# pcb_univ_3-6-0-x-rev5.net
KiCad netlist of a schematic drawn in EAGLE
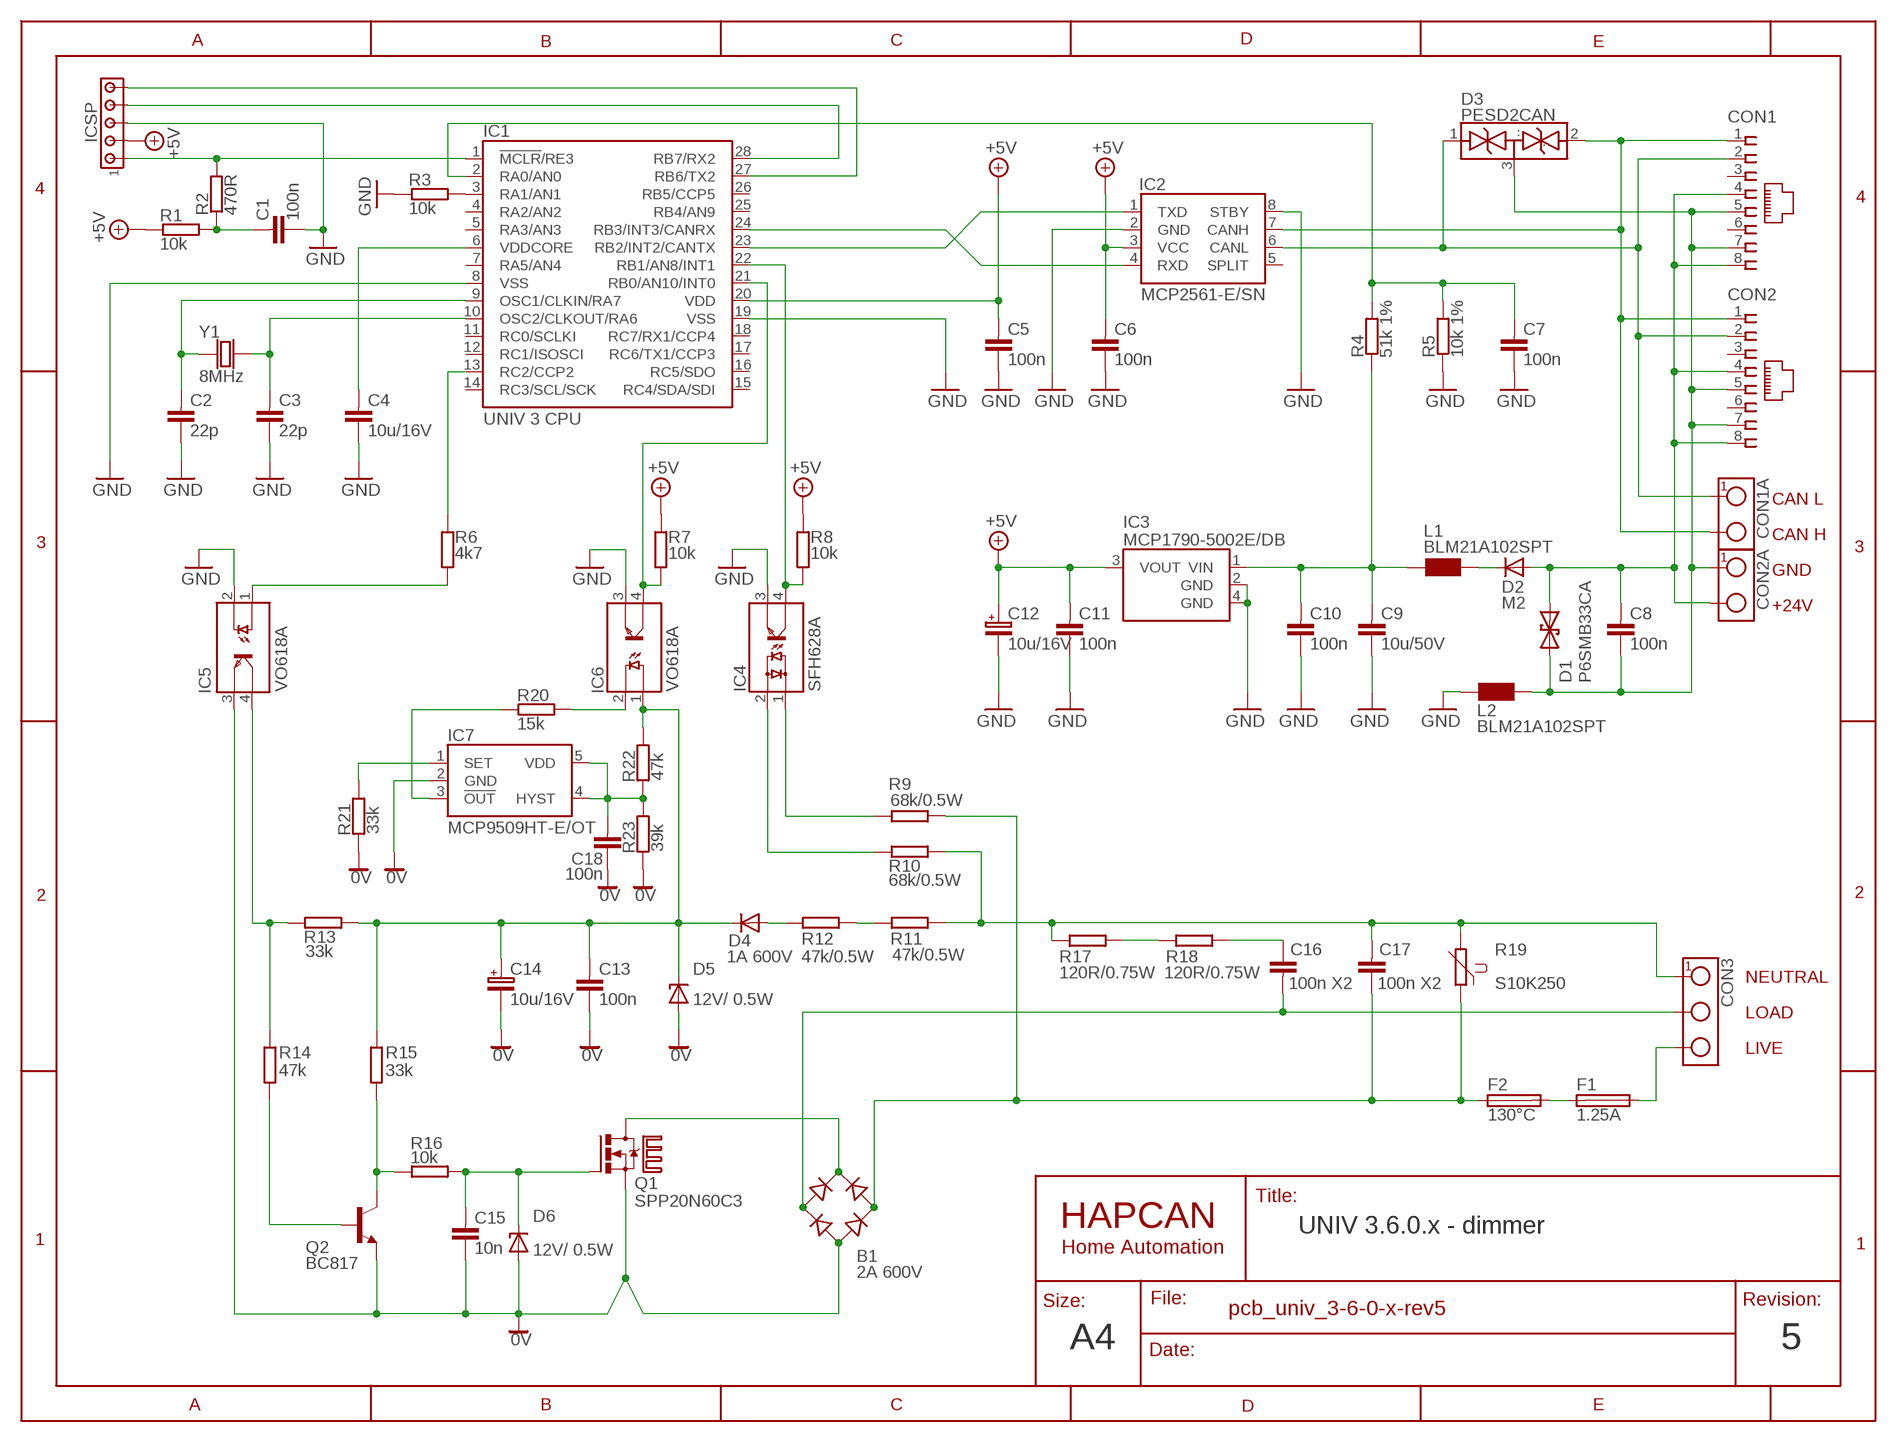
[diagram p0: schematic, sheet 1]

(export (version "E")
  (design (tool "Eeschema 10.0.6"))
  (components
    (comp (ref "B1")
      (value "2A 600V")
      (footprint "eagle-import:RECTIFIER_KBP")
      (libsource (lib "eagle-import") (part "DIODE_BRIDGE-5.0"))
    )
    (comp (ref "C1")
      (value "100n")
      (footprint "eagle-import:0805")
      (libsource (lib "eagle-import") (part "CAPACITOR0805"))
    )
    (comp (ref "C2")
      (value "22p")
      (footprint "eagle-import:0805")
      (libsource (lib "eagle-import") (part "CAPACITOR0805"))
    )
    (comp (ref "C3")
      (value "22p")
      (footprint "eagle-import:0805")
      (libsource (lib "eagle-import") (part "CAPACITOR0805"))
    )
    (comp (ref "C4")
      (value "10u/16V")
      (footprint "eagle-import:0805")
      (libsource (lib "eagle-import") (part "CAPACITOR0805"))
    )
    (comp (ref "C5")
      (value "100n")
      (footprint "eagle-import:0805")
      (libsource (lib "eagle-import") (part "CAPACITOR0805"))
    )
    (comp (ref "C6")
      (value "100n")
      (footprint "eagle-import:0805")
      (libsource (lib "eagle-import") (part "CAPACITOR0805"))
    )
    (comp (ref "C7")
      (value "100n")
      (footprint "eagle-import:0805")
      (libsource (lib "eagle-import") (part "CAPACITOR0805"))
    )
    (comp (ref "C8")
      (value "100n")
      (footprint "eagle-import:0805")
      (libsource (lib "eagle-import") (part "CAPACITOR0805"))
    )
    (comp (ref "C9")
      (value "10u/50V")
      (footprint "eagle-import:1210")
      (libsource (lib "eagle-import") (part "CAPACITOR1210"))
    )
    (comp (ref "C10")
      (value "100n")
      (footprint "eagle-import:0805")
      (libsource (lib "eagle-import") (part "CAPACITOR0805"))
    )
    (comp (ref "C11")
      (value "100n")
      (footprint "eagle-import:0805")
      (libsource (lib "eagle-import") (part "CAPACITOR0805"))
    )
    (comp (ref "C12")
      (value "10u/16V")
      (footprint "eagle-import:SMC_B")
      (libsource (lib "eagle-import") (part "CAPACITOR-POLARIZED-SMC_B"))
    )
    (comp (ref "C13")
      (value "100n")
      (footprint "eagle-import:0805")
      (libsource (lib "eagle-import") (part "CAPACITOR0805"))
    )
    (comp (ref "C14")
      (value "10u/16V")
      (footprint "eagle-import:SMC_B")
      (libsource (lib "eagle-import") (part "CAPACITOR-POLARIZED-SMC_B"))
    )
    (comp (ref "C15")
      (value "10n")
      (footprint "eagle-import:0805")
      (libsource (lib "eagle-import") (part "CAPACITOR0805"))
    )
    (comp (ref "C16")
      (value "100n X2")
      (footprint "eagle-import:CAP-15X5")
      (libsource (lib "eagle-import") (part "CAPACITOR15X5"))
    )
    (comp (ref "C17")
      (value "100n X2")
      (footprint "eagle-import:CAP-15X5")
      (libsource (lib "eagle-import") (part "CAPACITOR15X5"))
    )
    (comp (ref "C18")
      (value "100n")
      (footprint "eagle-import:0805")
      (libsource (lib "eagle-import") (part "CAPACITOR0805"))
    )
    (comp (ref "CON1")
      (value "RJ45-SOCKET")
      (footprint "eagle-import:RJ45-PCB-SOCKET")
      (libsource (lib "eagle-import") (part "RJ45-SOCKET"))
    )
    (comp (ref "CON1A")
      (value "TERMINAL-2")
      (footprint "eagle-import:ARK2-5X10,5MM")
      (libsource (lib "eagle-import") (part "TERMINAL-2-5X10,5MM"))
    )
    (comp (ref "CON2")
      (value "RJ45-SOCKET")
      (footprint "eagle-import:RJ45-PCB-SOCKET")
      (libsource (lib "eagle-import") (part "RJ45-SOCKET"))
    )
    (comp (ref "CON2A")
      (value "TERMINAL-2")
      (footprint "eagle-import:ARK2-5X10,5MM")
      (libsource (lib "eagle-import") (part "TERMINAL-2-5X10,5MM"))
    )
    (comp (ref "CON3")
      (value "TERMINAL-3")
      (footprint "eagle-import:ARK3-5X10.5MM")
      (libsource (lib "eagle-import") (part "TERMINAL-3-5X10.5MM"))
    )
    (comp (ref "D1")
      (value "P6SMB33CA")
      (footprint "eagle-import:DO-214_TRANSIL2")
      (libsource (lib "eagle-import") (part "DIODE_TRANSIL2"))
    )
    (comp (ref "D2")
      (value "M2")
      (footprint "eagle-import:DO-214")
      (libsource (lib "eagle-import") (part "DIODE_DO-214"))
    )
    (comp (ref "D3")
      (value "PESD2CAN")
      (footprint "eagle-import:SOT-23")
      (libsource (lib "eagle-import") (part "PESD2CANSOT-23"))
    )
    (comp (ref "D4")
      (value "1A 600V")
      (footprint "eagle-import:DO-213")
      (libsource (lib "eagle-import") (part "DIODE_MELF"))
    )
    (comp (ref "D5")
      (value "12V/ 0.5W")
      (footprint "eagle-import:SOD-80")
      (libsource (lib "eagle-import") (part "DIODE_ZENER_SOD-80"))
    )
    (comp (ref "D6")
      (value "12V/ 0.5W")
      (footprint "eagle-import:SOD-80")
      (libsource (lib "eagle-import") (part "DIODE_ZENER_SOD-80"))
    )
    (comp (ref "F1")
      (value "1.25A")
      (footprint "eagle-import:FUSE-HOLDER-V")
      (libsource (lib "eagle-import") (part "FUSE_V"))
    )
    (comp (ref "F2")
      (value "130°C")
      (footprint "eagle-import:FUSE-7.5")
      (libsource (lib "eagle-import") (part "FUSE"))
    )
    (comp (ref "IC1")
      (value "UNIV 3 CPU")
      (footprint "eagle-import:UNIV3CPU")
      (libsource (lib "eagle-import") (part "UNIV3CPU-I/SO"))
    )
    (comp (ref "IC2")
      (value "MCP2561-E/SN")
      (footprint "eagle-import:SO-08")
      (libsource (lib "eagle-import") (part "MCP2561-E/SN"))
    )
    (comp (ref "IC3")
      (value "MCP1790-5002E/DB")
      (footprint "eagle-import:SOT-223")
      (libsource (lib "eagle-import") (part "MCP1790"))
    )
    (comp (ref "IC4")
      (value "SFH628A")
      (footprint "eagle-import:DIL-04W")
      (libsource (lib "eagle-import") (part "COUPLER-1CH-AC_WIDE"))
    )
    (comp (ref "IC5")
      (value "VO618A")
      (footprint "eagle-import:DIL-04W")
      (libsource (lib "eagle-import") (part "COUPLER-1CH_04W"))
    )
    (comp (ref "IC6")
      (value "VO618A")
      (footprint "eagle-import:DIL-04W")
      (libsource (lib "eagle-import") (part "COUPLER-1CH_04W"))
    )
    (comp (ref "IC7")
      (value "MCP9509HT-E/OT")
      (footprint "eagle-import:SOT-23-5")
      (libsource (lib "eagle-import") (part "MCP9509"))
    )
    (comp (ref "ICSP")
      (value "HEADER5")
      (footprint "eagle-import:SIP-5")
      (libsource (lib "eagle-import") (part "HEADER5"))
    )
    (comp (ref "L1")
      (value "BLM21A102SPT")
      (footprint "eagle-import:0805")
      (libsource (lib "eagle-import") (part "CHOKE0805"))
    )
    (comp (ref "L2")
      (value "BLM21A102SPT")
      (footprint "eagle-import:0805")
      (libsource (lib "eagle-import") (part "CHOKE0805"))
    )
    (comp (ref "Q1")
      (value "SPP20N60C3")
      (footprint "eagle-import:TO220V-3")
      (libsource (lib "eagle-import") (part "TRANSISTOR_MOSFET_N_TO220V-3"))
    )
    (comp (ref "Q2")
      (value "BC817")
      (footprint "eagle-import:SOT-23")
      (libsource (lib "eagle-import") (part "TRANSISTOR_NPN"))
    )
    (comp (ref "R1")
      (value "10k")
      (footprint "eagle-import:0805")
      (libsource (lib "eagle-import") (part "RESISTOR0805"))
    )
    (comp (ref "R2")
      (value "470R")
      (footprint "eagle-import:0805")
      (libsource (lib "eagle-import") (part "RESISTOR0805"))
    )
    (comp (ref "R3")
      (value "10k")
      (footprint "eagle-import:0805")
      (libsource (lib "eagle-import") (part "RESISTOR0805"))
    )
    (comp (ref "R4")
      (value "51k 1%")
      (footprint "eagle-import:0805")
      (libsource (lib "eagle-import") (part "RESISTOR0805"))
    )
    (comp (ref "R5")
      (value "10k 1%")
      (footprint "eagle-import:0805")
      (libsource (lib "eagle-import") (part "RESISTOR0805"))
    )
    (comp (ref "R6")
      (value "4k7")
      (footprint "eagle-import:0805")
      (libsource (lib "eagle-import") (part "RESISTOR0805"))
    )
    (comp (ref "R7")
      (value "10k")
      (footprint "eagle-import:0805")
      (libsource (lib "eagle-import") (part "RESISTOR0805"))
    )
    (comp (ref "R8")
      (value "10k")
      (footprint "eagle-import:0805")
      (libsource (lib "eagle-import") (part "RESISTOR0805"))
    )
    (comp (ref "R9")
      (value "68k/0.5W")
      (footprint "eagle-import:2010")
      (libsource (lib "eagle-import") (part "RESISTOR2010"))
    )
    (comp (ref "R10")
      (value "68k/0.5W")
      (footprint "eagle-import:2010")
      (libsource (lib "eagle-import") (part "RESISTOR2010"))
    )
    (comp (ref "R11")
      (value "47k/0.5W")
      (footprint "eagle-import:2010")
      (libsource (lib "eagle-import") (part "RESISTOR2010"))
    )
    (comp (ref "R12")
      (value "47k/0.5W")
      (footprint "eagle-import:2010")
      (libsource (lib "eagle-import") (part "RESISTOR2010"))
    )
    (comp (ref "R13")
      (value "33k")
      (footprint "eagle-import:0805")
      (libsource (lib "eagle-import") (part "RESISTOR0805"))
    )
    (comp (ref "R14")
      (value "47k")
      (footprint "eagle-import:0805")
      (libsource (lib "eagle-import") (part "RESISTOR0805"))
    )
    (comp (ref "R15")
      (value "33k")
      (footprint "eagle-import:0805")
      (libsource (lib "eagle-import") (part "RESISTOR0805"))
    )
    (comp (ref "R16")
      (value "10k")
      (footprint "eagle-import:0805")
      (libsource (lib "eagle-import") (part "RESISTOR0805"))
    )
    (comp (ref "R17")
      (value "120R/0.75W")
      (footprint "eagle-import:2010")
      (libsource (lib "eagle-import") (part "RESISTOR2010"))
    )
    (comp (ref "R18")
      (value "120R/0.75W")
      (footprint "eagle-import:2010")
      (libsource (lib "eagle-import") (part "RESISTOR2010"))
    )
    (comp (ref "R19")
      (value "S10K250")
      (footprint "eagle-import:VARISTOR3")
      (libsource (lib "eagle-import") (part "VARISTOR7.5MM-2"))
    )
    (comp (ref "R20")
      (value "15k")
      (footprint "eagle-import:0805")
      (libsource (lib "eagle-import") (part "RESISTOR0805"))
    )
    (comp (ref "R21")
      (value "33k")
      (footprint "eagle-import:0805")
      (libsource (lib "eagle-import") (part "RESISTOR0805"))
    )
    (comp (ref "R22")
      (value "47k")
      (footprint "eagle-import:0805")
      (libsource (lib "eagle-import") (part "RESISTOR0805"))
    )
    (comp (ref "R23")
      (value "39k")
      (footprint "eagle-import:0805")
      (libsource (lib "eagle-import") (part "RESISTOR0805"))
    )
    (comp (ref "U$1")
      (value "HEATSINK_HS003")
      (footprint "eagle-import:HEATSINK_HS-003")
      (libsource (lib "eagle-import") (part "HEATSINK_HS003"))
    )
    (comp (ref "Y1")
      (value "8MHz")
      (footprint "eagle-import:CRYSTAL-HC49V")
      (libsource (lib "eagle-import") (part "CRYSTAL-HC49V"))
    )
  )
  (nets
    (net (code "1") (name "+5V") (class "Default")
      (node (ref "C11") (pin "1") (pinfunction "1_1") (pintype "passive"))
      (node (ref "C12") (pin "+") (pinfunction "1_+") (pintype "passive"))
      (node (ref "C5") (pin "1") (pinfunction "1_1") (pintype "passive"))
      (node (ref "C6") (pin "1") (pinfunction "1_1") (pintype "passive"))
      (node (ref "IC1") (pin "20") (pinfunction "VDD_20") (pintype "bidirectional"))
      (node (ref "IC2") (pin "3") (pinfunction "VCC_3") (pintype "bidirectional"))
      (node (ref "IC3") (pin "3") (pinfunction "VOUT_3") (pintype "bidirectional"))
      (node (ref "ICSP") (pin "2") (pinfunction "2_2") (pintype "passive"))
      (node (ref "R1") (pin "1") (pinfunction "1_1") (pintype "passive"))
      (node (ref "R7") (pin "2") (pinfunction "2_2") (pintype "passive"))
      (node (ref "R8") (pin "2") (pinfunction "2_2") (pintype "passive"))
    )
    (net (code "2") (name "0V") (class "Default")
      (node (ref "B1") (pin "-") (pinfunction "-_-") (pintype "passive"))
      (node (ref "C13") (pin "2") (pinfunction "2_2") (pintype "passive"))
      (node (ref "C14") (pin "-") (pinfunction "2_-") (pintype "passive"))
      (node (ref "C15") (pin "2") (pinfunction "2_2") (pintype "passive"))
      (node (ref "C18") (pin "2") (pinfunction "2_2") (pintype "passive"))
      (node (ref "D5") (pin "A") (pinfunction "A_A") (pintype "passive"))
      (node (ref "D6") (pin "A") (pinfunction "A_A") (pintype "passive"))
      (node (ref "IC5") (pin "3") (pinfunction "E_3") (pintype "bidirectional"))
      (node (ref "IC7") (pin "2") (pinfunction "GND_2") (pintype "bidirectional"))
      (node (ref "Q1") (pin "3") (pinfunction "S_3") (pintype "passive"))
      (node (ref "Q2") (pin "2") (pinfunction "E_2") (pintype "passive"))
      (node (ref "R21") (pin "2") (pinfunction "2_2") (pintype "passive"))
      (node (ref "R23") (pin "2") (pinfunction "2_2") (pintype "passive"))
    )
    (net (code "3") (name "GND") (class "Default")
      (node (ref "C1") (pin "2") (pinfunction "2_2") (pintype "passive"))
      (node (ref "C10") (pin "2") (pinfunction "2_2") (pintype "passive"))
      (node (ref "C11") (pin "2") (pinfunction "2_2") (pintype "passive"))
      (node (ref "C12") (pin "-") (pinfunction "2_-") (pintype "passive"))
      (node (ref "C2") (pin "2") (pinfunction "2_2") (pintype "passive"))
      (node (ref "C3") (pin "2") (pinfunction "2_2") (pintype "passive"))
      (node (ref "C4") (pin "2") (pinfunction "2_2") (pintype "passive"))
      (node (ref "C5") (pin "2") (pinfunction "2_2") (pintype "passive"))
      (node (ref "C6") (pin "2") (pinfunction "2_2") (pintype "passive"))
      (node (ref "C7") (pin "2") (pinfunction "2_2") (pintype "passive"))
      (node (ref "C9") (pin "2") (pinfunction "2_2") (pintype "passive"))
      (node (ref "IC1") (pin "19") (pinfunction "VSS_19") (pintype "bidirectional"))
      (node (ref "IC1") (pin "8") (pinfunction "VSS_8") (pintype "bidirectional"))
      (node (ref "IC2") (pin "2") (pinfunction "GND_2") (pintype "bidirectional"))
      (node (ref "IC2") (pin "8") (pinfunction "STBY_8") (pintype "bidirectional"))
      (node (ref "IC3") (pin "2") (pinfunction "GND_2") (pintype "bidirectional"))
      (node (ref "IC3") (pin "4") (pinfunction "GND_4") (pintype "bidirectional"))
      (node (ref "IC4") (pin "3") (pinfunction "E1_3") (pintype "bidirectional"))
      (node (ref "IC5") (pin "2") (pinfunction "K_2") (pintype "bidirectional"))
      (node (ref "IC6") (pin "3") (pinfunction "E_3") (pintype "bidirectional"))
      (node (ref "ICSP") (pin "3") (pinfunction "3_3") (pintype "passive"))
      (node (ref "L2") (pin "1") (pinfunction "1_1") (pintype "passive"))
      (node (ref "R3") (pin "1") (pinfunction "1_1") (pintype "passive"))
      (node (ref "R5") (pin "1") (pinfunction "1_1") (pintype "passive"))
    )
    (net (code "4") (name "Net-(B1-PadAC1)") (class "Default")
      (node (ref "B1") (pin "AC1") (pinfunction "AC1_AC1") (pintype "passive"))
      (node (ref "C16") (pin "1") (pinfunction "1_1") (pintype "passive"))
      (node (ref "CON3") (pin "2") (pinfunction "2_2") (pintype "passive"))
    )
    (net (code "5") (name "Net-(B1-PadAC2)") (class "Default")
      (node (ref "B1") (pin "AC2") (pinfunction "AC2_AC2") (pintype "passive"))
      (node (ref "C17") (pin "2") (pinfunction "2_2") (pintype "passive"))
      (node (ref "F2") (pin "1") (pinfunction "1_1") (pintype "passive"))
      (node (ref "R19") (pin "1") (pinfunction "1_1") (pintype "passive"))
      (node (ref "R9") (pin "2") (pinfunction "2_2") (pintype "passive"))
    )
    (net (code "6") (name "Net-(C1-Pad1)") (class "Default")
      (node (ref "C1") (pin "1") (pinfunction "1_1") (pintype "passive"))
      (node (ref "R1") (pin "2") (pinfunction "2_2") (pintype "passive"))
      (node (ref "R2") (pin "1") (pinfunction "1_1") (pintype "passive"))
    )
    (net (code "7") (name "Net-(C14-1)") (class "Default")
      (node (ref "C13") (pin "1") (pinfunction "1_1") (pintype "passive"))
      (node (ref "C14") (pin "+") (pinfunction "1_+") (pintype "passive"))
      (node (ref "D4") (pin "C") (pinfunction "C_C") (pintype "passive"))
      (node (ref "D5") (pin "C") (pinfunction "C_C") (pintype "passive"))
      (node (ref "IC6") (pin "1") (pinfunction "A_1") (pintype "bidirectional"))
      (node (ref "R13") (pin "2") (pinfunction "2_2") (pintype "passive"))
      (node (ref "R15") (pin "1") (pinfunction "1_1") (pintype "passive"))
      (node (ref "R22") (pin "2") (pinfunction "2_2") (pintype "passive"))
    )
    (net (code "8") (name "Net-(C16-Pad2)") (class "Default")
      (node (ref "C16") (pin "2") (pinfunction "2_2") (pintype "passive"))
      (node (ref "R18") (pin "1") (pinfunction "1_1") (pintype "passive"))
    )
    (net (code "9") (name "Net-(C17-Pad1)") (class "Default")
      (node (ref "C17") (pin "1") (pinfunction "1_1") (pintype "passive"))
      (node (ref "CON3") (pin "1") (pinfunction "1_1") (pintype "passive"))
      (node (ref "R10") (pin "2") (pinfunction "2_2") (pintype "passive"))
      (node (ref "R11") (pin "1") (pinfunction "1_1") (pintype "passive"))
      (node (ref "R17") (pin "2") (pinfunction "2_2") (pintype "passive"))
      (node (ref "R19") (pin "2") (pinfunction "2_2") (pintype "passive"))
    )
    (net (code "10") (name "Net-(CON3-Pad3)") (class "Default")
      (node (ref "CON3") (pin "3") (pinfunction "3_3") (pintype "passive"))
      (node (ref "F1") (pin "1") (pinfunction "1_1") (pintype "passive"))
    )
    (net (code "11") (name "Net-(D1-1)") (class "Default")
      (node (ref "C8") (pin "2") (pinfunction "2_2") (pintype "passive"))
      (node (ref "CON1") (pin "5") (pinfunction "5_5") (pintype "passive"))
      (node (ref "CON1") (pin "7") (pinfunction "7_7") (pintype "passive"))
      (node (ref "CON2") (pin "5") (pinfunction "5_5") (pintype "passive"))
      (node (ref "CON2") (pin "7") (pinfunction "7_7") (pintype "passive"))
      (node (ref "CON2A") (pin "1") (pinfunction "1_1") (pintype "passive"))
      (node (ref "D1") (pin "A") (pinfunction "1_A") (pintype "passive"))
      (node (ref "D3") (pin "3") (pinfunction "..._3") (pintype "bidirectional"))
      (node (ref "L2") (pin "2") (pinfunction "2_2") (pintype "passive"))
    )
    (net (code "12") (name "Net-(D1-2)") (class "Default")
      (node (ref "C8") (pin "1") (pinfunction "1_1") (pintype "passive"))
      (node (ref "CON1") (pin "4") (pinfunction "4_4") (pintype "passive"))
      (node (ref "CON1") (pin "8") (pinfunction "8_8") (pintype "passive"))
      (node (ref "CON2") (pin "4") (pinfunction "4_4") (pintype "passive"))
      (node (ref "CON2") (pin "8") (pinfunction "8_8") (pintype "passive"))
      (node (ref "CON2A") (pin "2") (pinfunction "2_2") (pintype "passive"))
      (node (ref "D1") (pin "C") (pinfunction "2_C") (pintype "passive"))
      (node (ref "D2") (pin "A") (pinfunction "A_A") (pintype "passive"))
    )
    (net (code "13") (name "Net-(D2-PadC)") (class "Default")
      (node (ref "D2") (pin "C") (pinfunction "C_C") (pintype "passive"))
      (node (ref "L1") (pin "2") (pinfunction "2_2") (pintype "passive"))
    )
    (net (code "14") (name "Net-(D3-.)") (class "Default")
      (node (ref "CON1") (pin "2") (pinfunction "2_2") (pintype "passive"))
      (node (ref "CON1A") (pin "1") (pinfunction "1_1") (pintype "passive"))
      (node (ref "CON2") (pin "2") (pinfunction "2_2") (pintype "passive"))
      (node (ref "D3") (pin "1") (pinfunction "._1") (pintype "bidirectional"))
      (node (ref "IC2") (pin "6") (pinfunction "CANL_6") (pintype "bidirectional"))
    )
    (net (code "15") (name "Net-(D3-..)") (class "Default")
      (node (ref "CON1") (pin "1") (pinfunction "1_1") (pintype "passive"))
      (node (ref "CON1A") (pin "2") (pinfunction "2_2") (pintype "passive"))
      (node (ref "CON2") (pin "1") (pinfunction "1_1") (pintype "passive"))
      (node (ref "D3") (pin "2") (pinfunction ".._2") (pintype "bidirectional"))
      (node (ref "IC2") (pin "7") (pinfunction "CANH_7") (pintype "bidirectional"))
    )
    (net (code "16") (name "Net-(D4-PadA)") (class "Default")
      (node (ref "D4") (pin "A") (pinfunction "A_A") (pintype "passive"))
      (node (ref "R12") (pin "2") (pinfunction "2_2") (pintype "passive"))
    )
    (net (code "17") (name "Net-(F1-Pad2)") (class "Default")
      (node (ref "F1") (pin "2") (pinfunction "2_2") (pintype "passive"))
      (node (ref "F2") (pin "2") (pinfunction "2_2") (pintype "passive"))
    )
    (net (code "18") (name "Net-(IC1-OSC1{slash}CLKIN{slash}RA7)") (class "Default")
      (node (ref "C2") (pin "1") (pinfunction "1_1") (pintype "passive"))
      (node (ref "IC1") (pin "9") (pinfunction "OSC1/CLKIN/RA7_9") (pintype "bidirectional"))
      (node (ref "Y1") (pin "1") (pinfunction "1_1") (pintype "passive"))
    )
    (net (code "19") (name "Net-(IC1-OSC2{slash}CLKOUT{slash}RA6)") (class "Default")
      (node (ref "C3") (pin "1") (pinfunction "1_1") (pintype "passive"))
      (node (ref "IC1") (pin "10") (pinfunction "OSC2/CLKOUT/RA6_10") (pintype "bidirectional"))
      (node (ref "Y1") (pin "2") (pinfunction "2_2") (pintype "passive"))
    )
    (net (code "20") (name "Net-(IC1-RA0{slash}AN0)") (class "Default")
      (node (ref "C7") (pin "1") (pinfunction "1_1") (pintype "passive"))
      (node (ref "IC1") (pin "2") (pinfunction "RA0/AN0_2") (pintype "bidirectional"))
      (node (ref "R4") (pin "2") (pinfunction "2_2") (pintype "passive"))
      (node (ref "R5") (pin "2") (pinfunction "2_2") (pintype "passive"))
    )
    (net (code "21") (name "Net-(IC1-RA1{slash}AN1)") (class "Default")
      (node (ref "IC1") (pin "3") (pinfunction "RA1/AN1_3") (pintype "bidirectional"))
      (node (ref "R3") (pin "2") (pinfunction "2_2") (pintype "passive"))
    )
    (net (code "22") (name "Net-(IC1-RB0{slash}AN10{slash}INT0)") (class "Default")
      (node (ref "IC1") (pin "21") (pinfunction "RB0/AN10/INT0_21") (pintype "bidirectional"))
      (node (ref "IC6") (pin "4") (pinfunction "C_4") (pintype "bidirectional"))
      (node (ref "R7") (pin "1") (pinfunction "1_1") (pintype "passive"))
    )
    (net (code "23") (name "Net-(IC1-RB1{slash}AN8{slash}INT1)") (class "Default")
      (node (ref "IC1") (pin "22") (pinfunction "RB1/AN8/INT1_22") (pintype "bidirectional"))
      (node (ref "IC4") (pin "4") (pinfunction "C1_4") (pintype "bidirectional"))
      (node (ref "R8") (pin "1") (pinfunction "1_1") (pintype "passive"))
    )
    (net (code "24") (name "Net-(IC1-RB2{slash}INT2{slash}CANTX)") (class "Default")
      (node (ref "IC1") (pin "23") (pinfunction "RB2/INT2/CANTX_23") (pintype "bidirectional"))
      (node (ref "IC2") (pin "1") (pinfunction "TXD_1") (pintype "bidirectional"))
    )
    (net (code "25") (name "Net-(IC1-RB3{slash}INT3{slash}CANRX)") (class "Default")
      (node (ref "IC1") (pin "24") (pinfunction "RB3/INT3/CANRX_24") (pintype "bidirectional"))
      (node (ref "IC2") (pin "4") (pinfunction "RXD_4") (pintype "bidirectional"))
    )
    (net (code "26") (name "Net-(IC1-RB6{slash}TX2)") (class "Default")
      (node (ref "IC1") (pin "27") (pinfunction "RB6/TX2_27") (pintype "bidirectional"))
      (node (ref "ICSP") (pin "5") (pinfunction "5_5") (pintype "passive"))
    )
    (net (code "27") (name "Net-(IC1-RB7{slash}RX2)") (class "Default")
      (node (ref "IC1") (pin "28") (pinfunction "RB7/RX2_28") (pintype "bidirectional"))
      (node (ref "ICSP") (pin "4") (pinfunction "4_4") (pintype "passive"))
    )
    (net (code "28") (name "Net-(IC1-RC2{slash}CCP2)") (class "Default")
      (node (ref "IC1") (pin "13") (pinfunction "RC2/CCP2_13") (pintype "bidirectional"))
      (node (ref "R6") (pin "1") (pinfunction "1_1") (pintype "passive"))
    )
    (net (code "29") (name "Net-(IC1-VDDCORE)") (class "Default")
      (node (ref "C4") (pin "1") (pinfunction "1_1") (pintype "passive"))
      (node (ref "IC1") (pin "6") (pinfunction "VDDCORE_6") (pintype "bidirectional"))
    )
    (net (code "30") (name "Net-(IC1-~{MCLR}{slash}RE3)") (class "Default")
      (node (ref "IC1") (pin "1") (pinfunction "~{MCLR}/RE3_1") (pintype "bidirectional"))
      (node (ref "ICSP") (pin "1") (pinfunction "1_1") (pintype "passive"))
      (node (ref "R2") (pin "2") (pinfunction "2_2") (pintype "passive"))
    )
    (net (code "31") (name "Net-(IC3-VIN)") (class "Default")
      (node (ref "C10") (pin "1") (pinfunction "1_1") (pintype "passive"))
      (node (ref "C9") (pin "1") (pinfunction "1_1") (pintype "passive"))
      (node (ref "IC3") (pin "1") (pinfunction "VIN_1") (pintype "bidirectional"))
      (node (ref "L1") (pin "1") (pinfunction "1_1") (pintype "passive"))
      (node (ref "R4") (pin "1") (pinfunction "1_1") (pintype "passive"))
    )
    (net (code "32") (name "Net-(IC4-A1)") (class "Default")
      (node (ref "IC4") (pin "1") (pinfunction "A1_1") (pintype "bidirectional"))
      (node (ref "R9") (pin "1") (pinfunction "1_1") (pintype "passive"))
    )
    (net (code "33") (name "Net-(IC4-A2)") (class "Default")
      (node (ref "IC4") (pin "2") (pinfunction "A2_2") (pintype "bidirectional"))
      (node (ref "R10") (pin "1") (pinfunction "1_1") (pintype "passive"))
    )
    (net (code "34") (name "Net-(IC5-A)") (class "Default")
      (node (ref "IC5") (pin "1") (pinfunction "A_1") (pintype "bidirectional"))
      (node (ref "R6") (pin "2") (pinfunction "2_2") (pintype "passive"))
    )
    (net (code "35") (name "Net-(IC5-C)") (class "Default")
      (node (ref "IC5") (pin "4") (pinfunction "C_4") (pintype "bidirectional"))
      (node (ref "R13") (pin "1") (pinfunction "1_1") (pintype "passive"))
      (node (ref "R14") (pin "1") (pinfunction "1_1") (pintype "passive"))
    )
    (net (code "36") (name "Net-(IC6-K)") (class "Default")
      (node (ref "IC6") (pin "2") (pinfunction "K_2") (pintype "bidirectional"))
      (node (ref "R20") (pin "1") (pinfunction "1_1") (pintype "passive"))
    )
    (net (code "37") (name "Net-(IC7-HYST)") (class "Default")
      (node (ref "C18") (pin "1") (pinfunction "1_1") (pintype "passive"))
      (node (ref "IC7") (pin "4") (pinfunction "HYST_4") (pintype "bidirectional"))
      (node (ref "IC7") (pin "5") (pinfunction "VDD_5") (pintype "bidirectional"))
      (node (ref "R22") (pin "1") (pinfunction "1_1") (pintype "passive"))
      (node (ref "R23") (pin "1") (pinfunction "1_1") (pintype "passive"))
    )
    (net (code "38") (name "Net-(IC7-SET)") (class "Default")
      (node (ref "IC7") (pin "1") (pinfunction "SET_1") (pintype "bidirectional"))
      (node (ref "R21") (pin "1") (pinfunction "1_1") (pintype "passive"))
    )
    (net (code "39") (name "Net-(IC7-~{OUT})") (class "Default")
      (node (ref "IC7") (pin "3") (pinfunction "~{OUT}_3") (pintype "bidirectional"))
      (node (ref "R20") (pin "2") (pinfunction "2_2") (pintype "passive"))
    )
    (net (code "40") (name "Net-(Q1-D)") (class "Default")
      (node (ref "B1") (pin "+") (pinfunction "+_+") (pintype "passive"))
      (node (ref "Q1") (pin "2") (pinfunction "D_2") (pintype "passive"))
    )
    (net (code "41") (name "Net-(Q1-G)") (class "Default")
      (node (ref "C15") (pin "1") (pinfunction "1_1") (pintype "passive"))
      (node (ref "D6") (pin "C") (pinfunction "C_C") (pintype "passive"))
      (node (ref "Q1") (pin "1") (pinfunction "G_1") (pintype "passive"))
      (node (ref "R16") (pin "1") (pinfunction "1_1") (pintype "passive"))
    )
    (net (code "42") (name "Net-(Q2-B)") (class "Default")
      (node (ref "Q2") (pin "1") (pinfunction "B_1") (pintype "passive"))
      (node (ref "R14") (pin "2") (pinfunction "2_2") (pintype "passive"))
    )
    (net (code "43") (name "Net-(Q2-C)") (class "Default")
      (node (ref "Q2") (pin "3") (pinfunction "C_3") (pintype "passive"))
      (node (ref "R15") (pin "2") (pinfunction "2_2") (pintype "passive"))
      (node (ref "R16") (pin "2") (pinfunction "2_2") (pintype "passive"))
    )
    (net (code "44") (name "Net-(R11-Pad2)") (class "Default")
      (node (ref "R11") (pin "2") (pinfunction "2_2") (pintype "passive"))
      (node (ref "R12") (pin "1") (pinfunction "1_1") (pintype "passive"))
    )
    (net (code "45") (name "Net-(R17-Pad1)") (class "Default")
      (node (ref "R17") (pin "1") (pinfunction "1_1") (pintype "passive"))
      (node (ref "R18") (pin "2") (pinfunction "2_2") (pintype "passive"))
    )
    (net (code "46") (name "unconnected-(CON1-Pad3)") (class "Default")
      (node (ref "CON1") (pin "3") (pinfunction "3_3") (pintype "passive"))
    )
    (net (code "47") (name "unconnected-(CON1-Pad6)") (class "Default")
      (node (ref "CON1") (pin "6") (pinfunction "6_6") (pintype "passive"))
    )
    (net (code "48") (name "unconnected-(CON2-Pad3)") (class "Default")
      (node (ref "CON2") (pin "3") (pinfunction "3_3") (pintype "passive"))
    )
    (net (code "49") (name "unconnected-(CON2-Pad6)") (class "Default")
      (node (ref "CON2") (pin "6") (pinfunction "6_6") (pintype "passive"))
    )
    (net (code "50") (name "unconnected-(IC1-RA2{slash}AN2-Pad4)") (class "Default")
      (node (ref "IC1") (pin "4") (pinfunction "RA2/AN2_4") (pintype "bidirectional"))
    )
    (net (code "51") (name "unconnected-(IC1-RA3{slash}AN3-Pad5)") (class "Default")
      (node (ref "IC1") (pin "5") (pinfunction "RA3/AN3_5") (pintype "bidirectional"))
    )
    (net (code "52") (name "unconnected-(IC1-RA5{slash}AN4-Pad7)") (class "Default")
      (node (ref "IC1") (pin "7") (pinfunction "RA5/AN4_7") (pintype "bidirectional"))
    )
    (net (code "53") (name "unconnected-(IC1-RB4{slash}AN9-Pad25)") (class "Default")
      (node (ref "IC1") (pin "25") (pinfunction "RB4/AN9_25") (pintype "bidirectional"))
    )
    (net (code "54") (name "unconnected-(IC1-RB5{slash}CCP5-Pad26)") (class "Default")
      (node (ref "IC1") (pin "26") (pinfunction "RB5/CCP5_26") (pintype "bidirectional"))
    )
    (net (code "55") (name "unconnected-(IC1-RC0{slash}SCLKI-Pad11)") (class "Default")
      (node (ref "IC1") (pin "11") (pinfunction "RC0/SCLKI_11") (pintype "bidirectional"))
    )
    (net (code "56") (name "unconnected-(IC1-RC1{slash}ISOSCI-Pad12)") (class "Default")
      (node (ref "IC1") (pin "12") (pinfunction "RC1/ISOSCI_12") (pintype "bidirectional"))
    )
    (net (code "57") (name "unconnected-(IC1-RC3{slash}SCL{slash}SCK-Pad14)") (class "Default")
      (node (ref "IC1") (pin "14") (pinfunction "RC3/SCL/SCK_14") (pintype "bidirectional"))
    )
    (net (code "58") (name "unconnected-(IC1-RC4{slash}SDA{slash}SDI-Pad15)") (class "Default")
      (node (ref "IC1") (pin "15") (pinfunction "RC4/SDA/SDI_15") (pintype "bidirectional"))
    )
    (net (code "59") (name "unconnected-(IC1-RC5{slash}SDO-Pad16)") (class "Default")
      (node (ref "IC1") (pin "16") (pinfunction "RC5/SDO_16") (pintype "bidirectional"))
    )
    (net (code "60") (name "unconnected-(IC1-RC6{slash}TX1{slash}CCP3-Pad17)") (class "Default")
      (node (ref "IC1") (pin "17") (pinfunction "RC6/TX1/CCP3_17") (pintype "bidirectional"))
    )
    (net (code "61") (name "unconnected-(IC1-RC7{slash}RX1{slash}CCP4-Pad18)") (class "Default")
      (node (ref "IC1") (pin "18") (pinfunction "RC7/RX1/CCP4_18") (pintype "bidirectional"))
    )
    (net (code "62") (name "unconnected-(IC2-SPLIT-Pad5)") (class "Default")
      (node (ref "IC2") (pin "5") (pinfunction "SPLIT_5") (pintype "bidirectional"))
    )
  )
)
